# cc2650_simplified.net
KiCad netlist of a schematic drawn in EAGLE
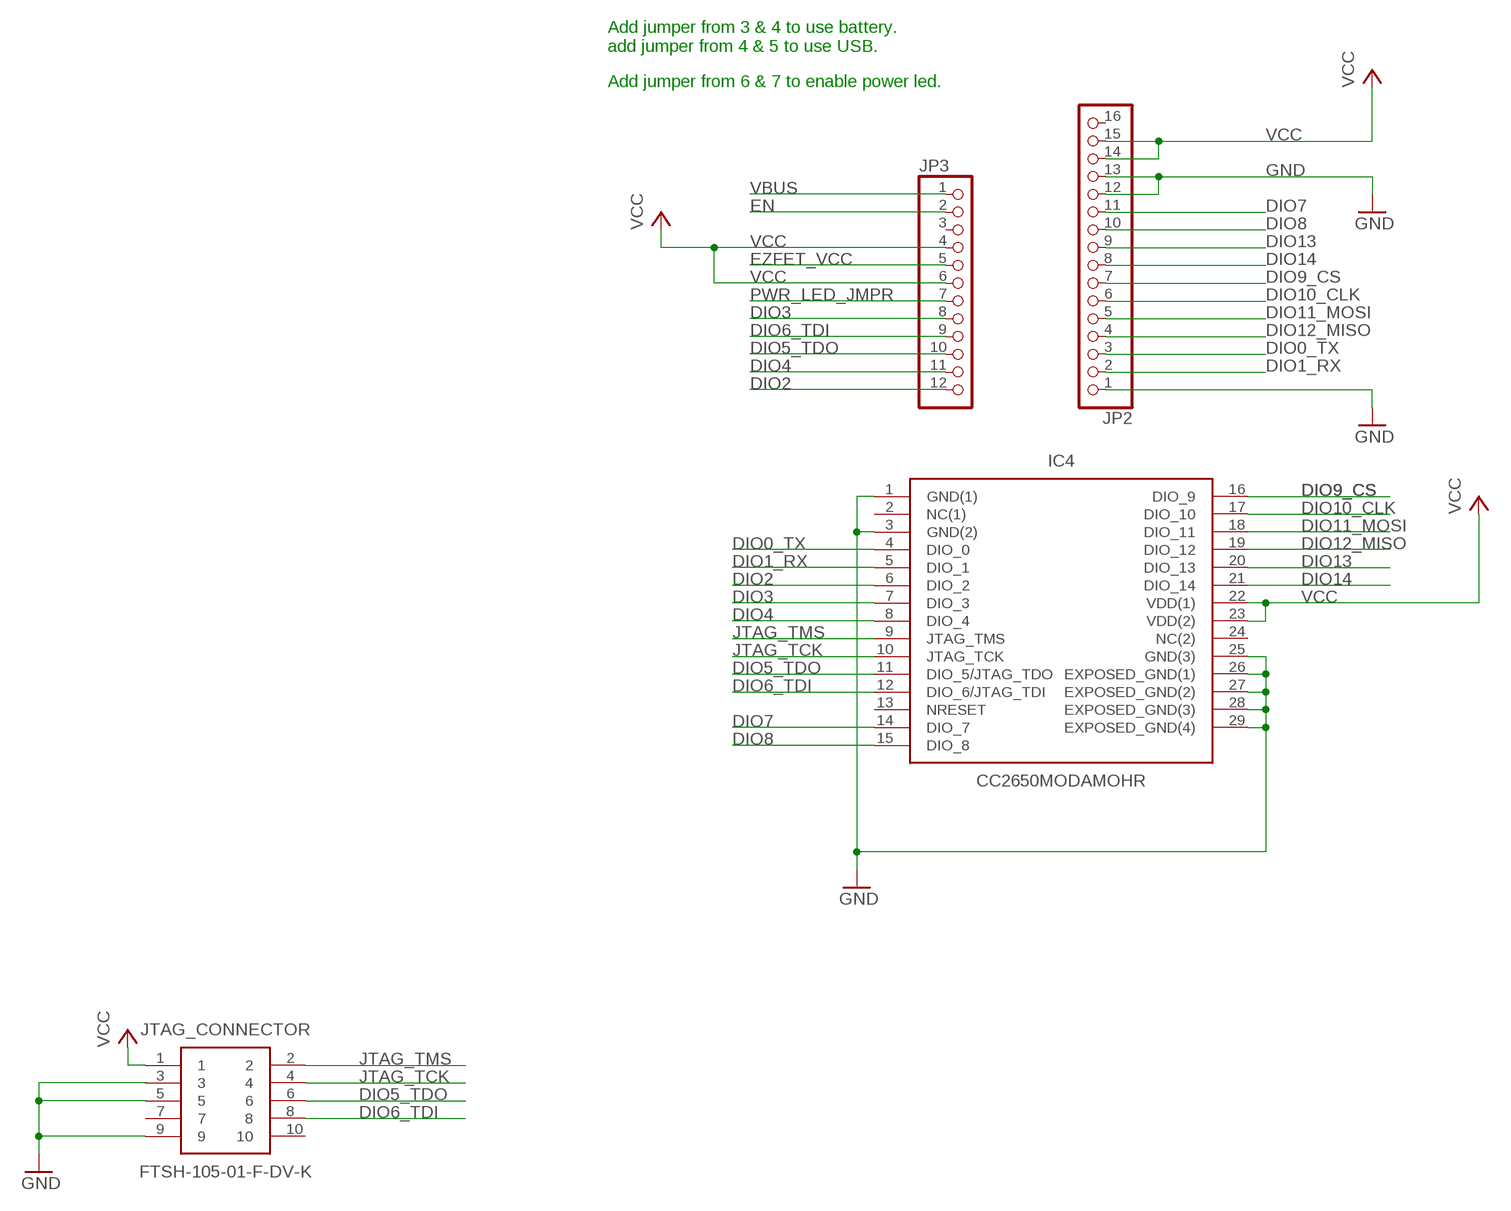
[diagram p0: schematic, sheet 1, part 1 of 2]
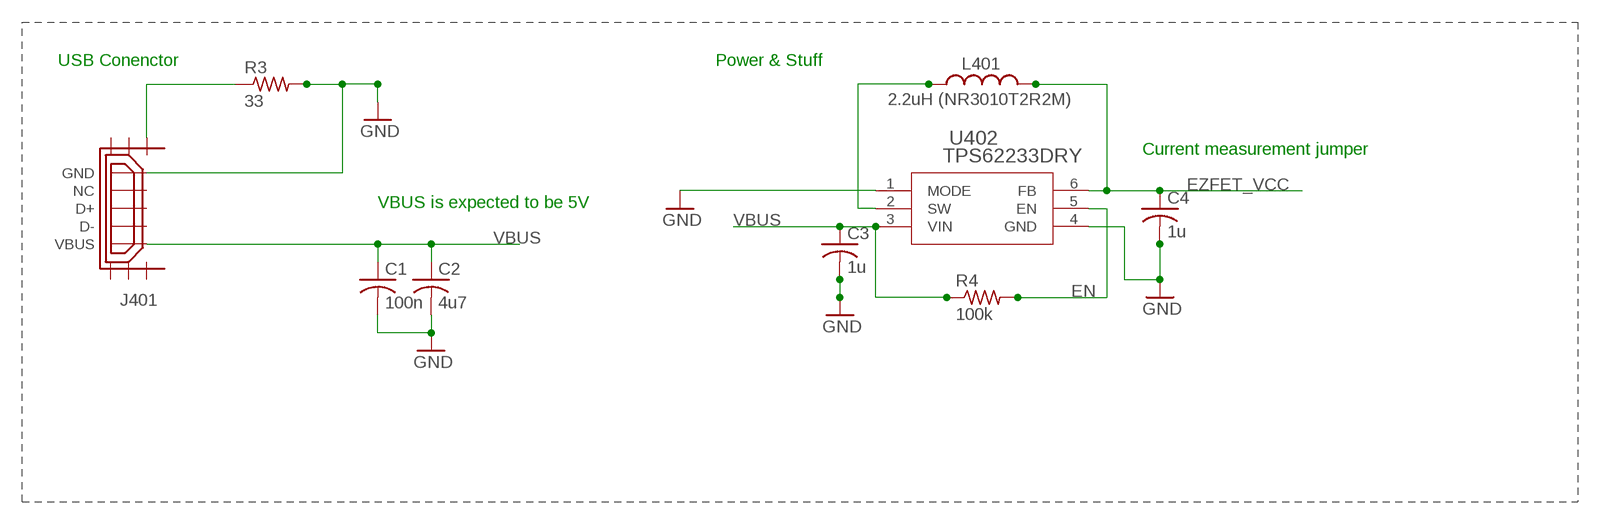
[diagram p1: schematic, sheet 1, part 2 of 2]

(export (version "E")
  (design (tool "Eeschema 10.0.6"))
  (components
    (comp (ref "C1")
      (value "100n")
      (footprint "eagle-import:C0402")
      (fields (field (name "MPN") "C1005X7R1H104K050BB"))
      (libsource (lib "eagle-import") (part "C-USC0402"))
    )
    (comp (ref "C2")
      (value "4u7")
      (footprint "eagle-import:C1206")
      (fields (field (name "MPN") "GRT31CC81E475KE01L"))
      (libsource (lib "eagle-import") (part "C-USC1206"))
    )
    (comp (ref "C3")
      (value "1u")
      (footprint "eagle-import:C0805")
      (fields (field (name "MPN") "C0805C105K5RACTU"))
      (libsource (lib "eagle-import") (part "C-USC0805"))
    )
    (comp (ref "C4")
      (value "1u")
      (footprint "eagle-import:C0805")
      (fields (field (name "MPN") "C0805C105K5RACTU"))
      (libsource (lib "eagle-import") (part "C-USC0805"))
    )
    (comp (ref "IC4")
      (value "CC2650MODAMOHR")
      (footprint "eagle-import:MOH0029A")
      (libsource (lib "eagle-import") (part "CC2650MODAMOHR"))
    )
    (comp (ref "J401")
      (value "USB_MICRO_FLIPPED")
      (footprint "eagle-import:HIROSE-ZX62R-B-5P")
      (fields (field (name "MPN") "ZX62R-B-5P(30)"))
      (libsource (lib "eagle-import") (part "USB_MICRO_FLIPPED"))
    )
    (comp (ref "JP2")
      (value "HEADER-1X16ROUND")
      (footprint "eagle-import:1X16_ROUND")
      (libsource (lib "eagle-import") (part "HEADER-1X16ROUND"))
    )
    (comp (ref "JP3")
      (value "HEADER-1X12")
      (footprint "eagle-import:1X12_ROUND")
      (libsource (lib "eagle-import") (part "HEADER-1X12"))
    )
    (comp (ref "JTAG_CONNECTOR")
      (value "FTSH-105-01-F-DV-K")
      (footprint "eagle-import:SAMTEC_FTSH-105-01-L-DV")
      (libsource (lib "eagle-import") (part "FTSH-105-01-F-DV-K"))
    )
    (comp (ref "L401")
      (value "2.2uH (NR3010T2R2M)")
      (footprint "eagle-import:L-NR3010")
      (fields (field (name "MPN") "NR3010T2R2M"))
      (libsource (lib "eagle-import") (part "L-NR3010"))
    )
    (comp (ref "R3")
      (value "33")
      (footprint "eagle-import:R0402")
      (fields (field (name "MPN") "ERJ-U02F33R0X"))
      (libsource (lib "eagle-import") (part "R-US_R0402"))
    )
    (comp (ref "R4")
      (value "100k")
      (footprint "eagle-import:R0603")
      (fields (field (name "MPN") "RC0603JR-07100KL"))
      (libsource (lib "eagle-import") (part "R-US_R0603"))
    )
    (comp (ref "U402")
      (value "TPS62233DRY")
      (footprint "eagle-import:DRY6")
      (fields
        (field (name "GENERIC_PART_NUMBER") "TPS62231")
        (field (name "MANUFACTURER") "Texas Instruments")
        (field (name "MANUFACTURER_PART_NUMBER") "tps62231_dry_6")
      )
      (libsource (lib "eagle-import") (part "TPS6223X_DRY_6"))
    )
  )
  (nets
    (net (code "1") (name "/DIO0_TX") (class "Default")
      (node (ref "IC4") (pin "4") (pinfunction "DIO_0_4") (pintype "passive"))
      (node (ref "JP2") (pin "3") (pinfunction "3_3") (pintype "passive"))
    )
    (net (code "2") (name "/DIO1_RX") (class "Default")
      (node (ref "IC4") (pin "5") (pinfunction "DIO_1_5") (pintype "passive"))
      (node (ref "JP2") (pin "2") (pinfunction "2_2") (pintype "passive"))
    )
    (net (code "3") (name "/DIO2") (class "Default")
      (node (ref "IC4") (pin "6") (pinfunction "DIO_2_6") (pintype "passive"))
      (node (ref "JP3") (pin "12") (pinfunction "12_12") (pintype "passive"))
    )
    (net (code "4") (name "/DIO3") (class "Default")
      (node (ref "IC4") (pin "7") (pinfunction "DIO_3_7") (pintype "passive"))
      (node (ref "JP3") (pin "8") (pinfunction "8_8") (pintype "passive"))
    )
    (net (code "5") (name "/DIO4") (class "Default")
      (node (ref "IC4") (pin "8") (pinfunction "DIO_4_8") (pintype "passive"))
      (node (ref "JP3") (pin "11") (pinfunction "11_11") (pintype "passive"))
    )
    (net (code "6") (name "/DIO5_TDO") (class "Default")
      (node (ref "IC4") (pin "11") (pinfunction "DIO_5/JTAG_TDO_11") (pintype "passive"))
      (node (ref "JP3") (pin "10") (pinfunction "10_10") (pintype "passive"))
      (node (ref "JTAG_CONNECTOR") (pin "6") (pinfunction "6_6") (pintype "passive"))
    )
    (net (code "7") (name "/DIO6_TDI") (class "Default")
      (node (ref "IC4") (pin "12") (pinfunction "DIO_6/JTAG_TDI_12") (pintype "passive"))
      (node (ref "JP3") (pin "9") (pinfunction "9_9") (pintype "passive"))
      (node (ref "JTAG_CONNECTOR") (pin "8") (pinfunction "8_8") (pintype "passive"))
    )
    (net (code "8") (name "/DIO7") (class "Default")
      (node (ref "IC4") (pin "14") (pinfunction "DIO_7_14") (pintype "passive"))
      (node (ref "JP2") (pin "11") (pinfunction "11_11") (pintype "passive"))
    )
    (net (code "9") (name "/DIO8") (class "Default")
      (node (ref "IC4") (pin "15") (pinfunction "DIO_8_15") (pintype "passive"))
      (node (ref "JP2") (pin "10") (pinfunction "10_10") (pintype "passive"))
    )
    (net (code "10") (name "/DIO9_CS") (class "Default")
      (node (ref "IC4") (pin "16") (pinfunction "DIO_9_16") (pintype "passive"))
      (node (ref "JP2") (pin "7") (pinfunction "7_7") (pintype "passive"))
    )
    (net (code "11") (name "/DIO10_CLK") (class "Default")
      (node (ref "IC4") (pin "17") (pinfunction "DIO_10_17") (pintype "passive"))
      (node (ref "JP2") (pin "6") (pinfunction "6_6") (pintype "passive"))
    )
    (net (code "12") (name "/DIO11_MOSI") (class "Default")
      (node (ref "IC4") (pin "18") (pinfunction "DIO_11_18") (pintype "passive"))
      (node (ref "JP2") (pin "5") (pinfunction "5_5") (pintype "passive"))
    )
    (net (code "13") (name "/DIO12_MISO") (class "Default")
      (node (ref "IC4") (pin "19") (pinfunction "DIO_12_19") (pintype "passive"))
      (node (ref "JP2") (pin "4") (pinfunction "4_4") (pintype "passive"))
    )
    (net (code "14") (name "/DIO13") (class "Default")
      (node (ref "IC4") (pin "20") (pinfunction "DIO_13_20") (pintype "passive"))
      (node (ref "JP2") (pin "9") (pinfunction "9_9") (pintype "passive"))
    )
    (net (code "15") (name "/DIO14") (class "Default")
      (node (ref "IC4") (pin "21") (pinfunction "DIO_14_21") (pintype "passive"))
      (node (ref "JP2") (pin "8") (pinfunction "8_8") (pintype "passive"))
    )
    (net (code "16") (name "/EN") (class "Default")
      (node (ref "JP3") (pin "2") (pinfunction "2_2") (pintype "passive"))
      (node (ref "R4") (pin "2") (pinfunction "2_2") (pintype "passive"))
      (node (ref "U402") (pin "5") (pinfunction "EN_5") (pintype "input"))
    )
    (net (code "17") (name "/EZFET_VCC") (class "Default")
      (node (ref "C4") (pin "1") (pinfunction "1_1") (pintype "passive"))
      (node (ref "JP3") (pin "5") (pinfunction "5_5") (pintype "passive"))
      (node (ref "L401") (pin "P$2") (pinfunction "2_P$2") (pintype "passive"))
      (node (ref "U402") (pin "6") (pinfunction "FB_6") (pintype "input"))
    )
    (net (code "18") (name "/JTAG_TCK") (class "Default")
      (node (ref "IC4") (pin "10") (pinfunction "JTAG_TCK_10") (pintype "passive"))
      (node (ref "JTAG_CONNECTOR") (pin "4") (pinfunction "4_4") (pintype "passive"))
    )
    (net (code "19") (name "/JTAG_TMS") (class "Default")
      (node (ref "IC4") (pin "9") (pinfunction "JTAG_TMS_9") (pintype "passive"))
      (node (ref "JTAG_CONNECTOR") (pin "2") (pinfunction "2_2") (pintype "passive"))
    )
    (net (code "20") (name "/PWR_LED_JMPR") (class "Default")
      (node (ref "JP3") (pin "7") (pinfunction "7_7") (pintype "passive"))
    )
    (net (code "21") (name "/VBUS") (class "Default")
      (node (ref "C1") (pin "1") (pinfunction "1_1") (pintype "passive"))
      (node (ref "C2") (pin "1") (pinfunction "1_1") (pintype "passive"))
      (node (ref "C3") (pin "1") (pinfunction "1_1") (pintype "passive"))
      (node (ref "J401") (pin "VBUS") (pinfunction "VBUS_VBUS") (pintype "input"))
      (node (ref "JP3") (pin "1") (pinfunction "1_1") (pintype "passive"))
      (node (ref "R4") (pin "1") (pinfunction "1_1") (pintype "passive"))
      (node (ref "U402") (pin "3") (pinfunction "VIN_3") (pintype "power_in"))
    )
    (net (code "22") (name "GND") (class "Default")
      (node (ref "C1") (pin "2") (pinfunction "2_2") (pintype "passive"))
      (node (ref "C2") (pin "2") (pinfunction "2_2") (pintype "passive"))
      (node (ref "C3") (pin "2") (pinfunction "2_2") (pintype "passive"))
      (node (ref "C4") (pin "2") (pinfunction "2_2") (pintype "passive"))
      (node (ref "IC4") (pin "1") (pinfunction "GND(1)_1") (pintype "passive"))
      (node (ref "IC4") (pin "25") (pinfunction "GND(3)_25") (pintype "passive"))
      (node (ref "IC4") (pin "26") (pinfunction "EXPOSED_GND(1)_26") (pintype "passive"))
      (node (ref "IC4") (pin "27") (pinfunction "EXPOSED_GND(2)_27") (pintype "passive"))
      (node (ref "IC4") (pin "28") (pinfunction "EXPOSED_GND(3)_28") (pintype "passive"))
      (node (ref "IC4") (pin "29") (pinfunction "EXPOSED_GND(4)_29") (pintype "passive"))
      (node (ref "IC4") (pin "3") (pinfunction "GND(2)_3") (pintype "passive"))
      (node (ref "J401") (pin "GND") (pinfunction "GND_GND") (pintype "input"))
      (node (ref "JP2") (pin "1") (pinfunction "1_1") (pintype "passive"))
      (node (ref "JP2") (pin "12") (pinfunction "12_12") (pintype "passive"))
      (node (ref "JP2") (pin "13") (pinfunction "13_13") (pintype "passive"))
      (node (ref "JTAG_CONNECTOR") (pin "3") (pinfunction "3_3") (pintype "passive"))
      (node (ref "JTAG_CONNECTOR") (pin "5") (pinfunction "5_5") (pintype "passive"))
      (node (ref "JTAG_CONNECTOR") (pin "9") (pinfunction "9_9") (pintype "passive"))
      (node (ref "R3") (pin "2") (pinfunction "2_2") (pintype "passive"))
      (node (ref "U402") (pin "1") (pinfunction "MODE_1") (pintype "input"))
      (node (ref "U402") (pin "4") (pinfunction "GND_4") (pintype "power_in"))
    )
    (net (code "23") (name "Net-(J401-PadSHIELD1)") (class "Default")
      (node (ref "J401") (pin "SHIELD1") (pinfunction "SHIELD1_SHIELD1") (pintype "bidirectional"))
      (node (ref "R3") (pin "1") (pinfunction "1_1") (pintype "passive"))
    )
    (net (code "24") (name "Net-(L401-1)") (class "Default")
      (node (ref "L401") (pin "P$1") (pinfunction "1_P$1") (pintype "passive"))
      (node (ref "U402") (pin "2") (pinfunction "SW_2") (pintype "output"))
    )
    (net (code "25") (name "VCC") (class "Default")
      (node (ref "IC4") (pin "22") (pinfunction "VDD(1)_22") (pintype "passive"))
      (node (ref "IC4") (pin "23") (pinfunction "VDD(2)_23") (pintype "passive"))
      (node (ref "JP2") (pin "14") (pinfunction "14_14") (pintype "passive"))
      (node (ref "JP2") (pin "15") (pinfunction "15_15") (pintype "passive"))
      (node (ref "JP3") (pin "4") (pinfunction "4_4") (pintype "passive"))
      (node (ref "JP3") (pin "6") (pinfunction "6_6") (pintype "passive"))
      (node (ref "JTAG_CONNECTOR") (pin "1") (pinfunction "1_1") (pintype "passive"))
    )
    (net (code "26") (name "unconnected-(IC4-NC(1)-Pad2)") (class "Default")
      (node (ref "IC4") (pin "2") (pinfunction "NC(1)_2") (pintype "passive"))
    )
    (net (code "27") (name "unconnected-(IC4-NC(2)-Pad24)") (class "Default")
      (node (ref "IC4") (pin "24") (pinfunction "NC(2)_24") (pintype "passive"))
    )
    (net (code "28") (name "unconnected-(IC4-NRESET-Pad13)") (class "Default")
      (node (ref "IC4") (pin "13") (pinfunction "NRESET_13") (pintype "passive"))
    )
    (net (code "29") (name "unconnected-(J401-PadD+)") (class "Default")
      (node (ref "J401") (pin "D+") (pinfunction "D+_D+") (pintype "input"))
    )
    (net (code "30") (name "unconnected-(J401-PadD-)") (class "Default")
      (node (ref "J401") (pin "D-") (pinfunction "D-_D-") (pintype "input"))
    )
    (net (code "31") (name "unconnected-(J401-PadNC)") (class "Default")
      (node (ref "J401") (pin "NC") (pinfunction "NC_NC") (pintype "input"))
    )
    (net (code "32") (name "unconnected-(J401-PadSHIELD2)") (class "Default")
      (node (ref "J401") (pin "SHIELD2") (pinfunction "SHIELD2_SHIELD2") (pintype "bidirectional"))
    )
    (net (code "33") (name "unconnected-(J401-PadSHIELD3)") (class "Default")
      (node (ref "J401") (pin "SHIELD3") (pinfunction "SHIELD3_SHIELD3") (pintype "bidirectional"))
    )
    (net (code "34") (name "unconnected-(J401-PadSHIELD4)") (class "Default")
      (node (ref "J401") (pin "SHIELD4") (pinfunction "SHIELD4_SHIELD4") (pintype "bidirectional"))
    )
    (net (code "35") (name "unconnected-(J401-PadSHIELD5)") (class "Default")
      (node (ref "J401") (pin "SHIELD5") (pinfunction "SHIELD5_SHIELD5") (pintype "bidirectional"))
    )
    (net (code "36") (name "unconnected-(J401-PadSHIELD6)") (class "Default")
      (node (ref "J401") (pin "SHIELD6") (pinfunction "SHIELD6_SHIELD6") (pintype "bidirectional"))
    )
    (net (code "37") (name "unconnected-(JP2-Pad16)") (class "Default")
      (node (ref "JP2") (pin "16") (pinfunction "16_16") (pintype "passive"))
    )
    (net (code "38") (name "unconnected-(JP3-Pad3)") (class "Default")
      (node (ref "JP3") (pin "3") (pinfunction "3_3") (pintype "passive"))
    )
    (net (code "39") (name "unconnected-(JTAG_CONNECTOR-Pad7)") (class "Default")
      (node (ref "JTAG_CONNECTOR") (pin "7") (pinfunction "7_7") (pintype "passive"))
    )
    (net (code "40") (name "unconnected-(JTAG_CONNECTOR-Pad10)") (class "Default")
      (node (ref "JTAG_CONNECTOR") (pin "10") (pinfunction "10_10") (pintype "passive"))
    )
  )
)
